# STLink_V3E_Module.net
KiCad netlist of a schematic drawn in Altium Designer
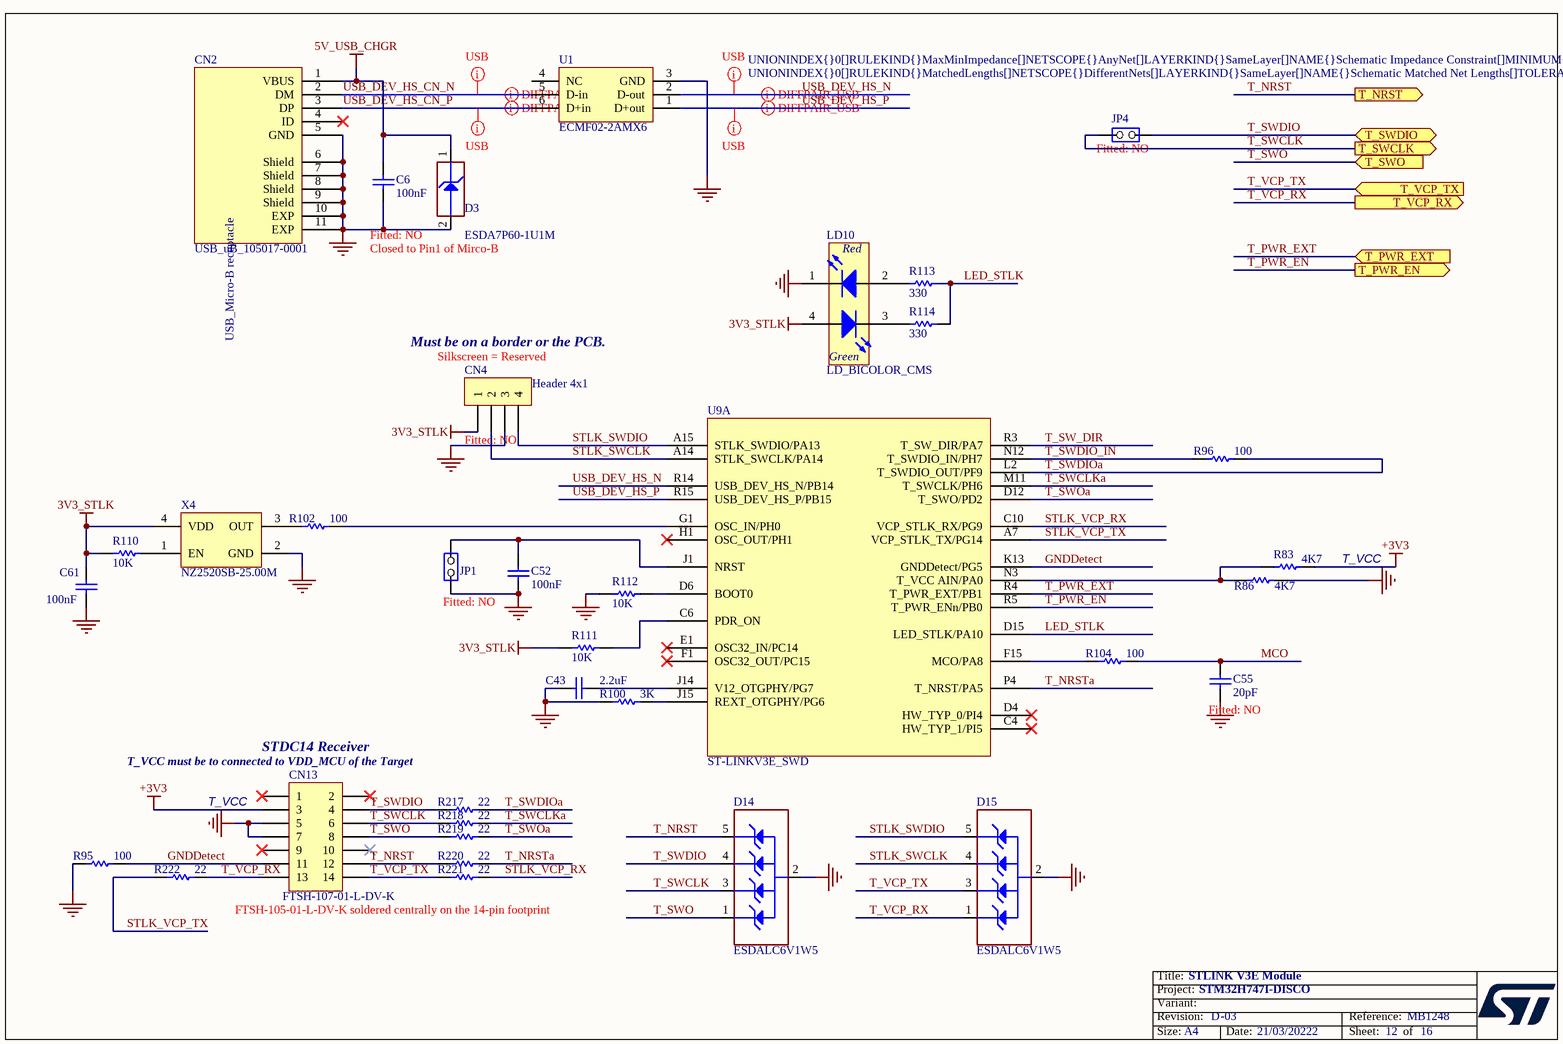
[diagram p0: STLink_V3E_Module.SchDoc]

(export (version "E")
  (design (tool "Eeschema 10.0.6"))
  (components
    (comp (ref "C6")
      (value "100nF")
      (footprint "0402C")
      (description "Capacitor,20pF,50V,NPO,5%,0402")
      (fields
        (field (name "INTERNAL_PART_NUMBER") "MCD-00016")
        (field (name "MANUFACTURER_PART_NUMBER") "CC0402JRNPO9BN200")
        (field (name "FITTED") "NO")
        (field (name "PROVIDED_BY") "Subcon")
      )
      (libsource (lib "MCD_PARTS_database") (part "Capacitor"))
    )
    (comp (ref "C43")
      (value "2.2uF")
      (footprint "0603C")
      (description "Capacitor,2.2uF,10V, X5R,10%,0603")
      (fields
        (field (name "INTERNAL_PART_NUMBER") "MCD-00012")
        (field (name "MANUFACTURER_PART_NUMBER") "CC0603KRX5R6BB225")
        (field (name "PROVIDED_BY") "Subcon")
      )
      (libsource (lib "MCD_PARTS_database") (part "Capacitor"))
    )
    (comp (ref "C52")
      (value "100nF")
      (footprint "0402C")
      (description "Capacitor,100nF,16V,X7R,10%,0402")
      (fields
        (field (name "INTERNAL_PART_NUMBER") "MCD-00102")
        (field (name "MANUFACTURER_PART_NUMBER") "CC0402KRX7R7BB104")
        (field (name "PROVIDED_BY") "Subcon")
      )
      (libsource (lib "MCD_PARTS_database") (part "Capacitor"))
    )
    (comp (ref "C55")
      (value "20pF")
      (footprint "0402C")
      (description "Capacitor,20pF,50V,NPO,5%,0402")
      (fields
        (field (name "INTERNAL_PART_NUMBER") "MCD-00016")
        (field (name "MANUFACTURER_PART_NUMBER") "CC0402JRNPO9BN200")
        (field (name "FITTED") "NO")
        (field (name "PROVIDED_BY") "Subcon")
      )
      (libsource (lib "MCD_PARTS_database") (part "Capacitor"))
    )
    (comp (ref "C61")
      (value "100nF")
      (footprint "0402C")
      (description "Capacitor,100nF,16V,X7R,10%,0402")
      (fields
        (field (name "INTERNAL_PART_NUMBER") "MCD-00102")
        (field (name "MANUFACTURER_PART_NUMBER") "CC0402KRX7R7BB104")
        (field (name "PROVIDED_BY") "Subcon")
      )
      (libsource (lib "MCD_PARTS_database") (part "Capacitor"))
    )
    (comp (ref "CN2")
      (value "USB_uB_105017-0001")
      (footprint "MICRO_USB_B_105017")
      (description "USB-MICRO-B, 0.65mm, RA, SMT, Bottom Mount,")
      (fields
        (field (name "INTERNAL_PART_NUMBER") "MCD-00028")
        (field (name "MANUFACTURER_PART_NUMBER") "1050170001")
        (field (name "PROVIDED_BY") "Subcon")
      )
      (libsource (lib "MCD_PARTS_database") (part "USB_uB_105017.0001"))
    )
    (comp (ref "CN4")
      (value "Header 4x1")
      (footprint "HDR_1X4_2R54")
      (description "Header, 4x1, 2,54mm, VR, TH, Height 5.84mm/2.54mm")
      (fields
        (field (name "INTERNAL_PART_NUMBER") "MCD-00029")
        (field (name "MANUFACTURER_PART_NUMBER") "TSW-104-07-x-S")
        (field (name "FITTED") "NO")
        (field (name "PROVIDED_BY") "Subcon")
      )
      (libsource (lib "MCD_PARTS_database") (part "Header 4x1"))
    )
    (comp (ref "CN13")
      (value "FTSH-107-01-L-DV-K")
      (footprint "FTSH-107-01-L-DV_B")
      (description "Header 7x2, 1.27mm, Dual row, Straight")
      (fields
        (field (name "INTERNAL_PART_NUMBER") "MCD-00592")
        (field (name "MANUFACTURER_PART_NUMBER") "FTSH-107-01-L-DV-009-ES-A")
        (field (name "PROVIDED_BY") "Subcon")
      )
      (libsource (lib "MCD_PARTS_database") (part "Header 7x2"))
    )
    (comp (ref "D3")
      (value "ESDA7P60-1U1M")
      (footprint "DO_2SM_1R6X1_21")
      (description "Dual Transil array for ESD protection")
      (libsource (lib "MCD_TEMP_PCH") (part "ESDALC6V1-1U2"))
    )
    (comp (ref "D14")
      (value "ESDALC6V1W5")
      (footprint "SC70-5")
      (description "Dual Transil array for ESD protection")
      (libsource (lib "MB1167_1") (part "ESDALC6V1W5"))
    )
    (comp (ref "D15")
      (value "ESDALC6V1W5")
      (footprint "SC70-5")
      (description "Dual Transil array for ESD protection")
      (libsource (lib "MB1167_1") (part "ESDALC6V1W5"))
    )
    (comp (ref "JP1")
      (value "Jumper Header 2x1")
      (footprint "SIP2")
      (description "Header, 2x1, 2,54mm, VR, TH, Height 5.84mm/2.54mm")
      (fields
        (field (name "INTERNAL_PART_NUMBER") "MCD-00045")
        (field (name "MANUFACTURER_PART_NUMBER") "TSW-102-07-x-S")
        (field (name "FITTED") "NO")
        (field (name "PROVIDED_BY") "Subcon")
      )
      (libsource (lib "MCD_PARTS_database") (part "Jumper Header 2x1"))
    )
    (comp (ref "JP4")
      (value "Jumper Header 2x1")
      (footprint "SIP2")
      (description "Header, 2x1, 2,54mm, VR, TH, Height 5.84mm/2.54mm")
      (fields
        (field (name "INTERNAL_PART_NUMBER") "MCD-00045")
        (field (name "MANUFACTURER_PART_NUMBER") "TSW-102-07-x-S")
        (field (name "FITTED") "NO")
        (field (name "PROVIDED_BY") "Subcon")
      )
      (libsource (lib "MCD_PARTS_database") (part "Jumper Header 2x1"))
    )
    (comp (ref "LD10")
      (value "LD_BICOLOR_CMS")
      (footprint "LED2_3528")
      (description "LED Bicolor")
      (fields
        (field (name "INTERNAL_PART_NUMBER") "MCD-00051")
        (field (name "MANUFACTURER_PART_NUMBER") "HSMF-A201-A00J1")
        (field (name "PROVIDED_BY") "Subcon")
      )
      (libsource (lib "MCD_PARTS_database") (part "LD_BICOLOR_CMS"))
    )
    (comp (ref "R83")
      (value "4K7")
      (footprint "0402R")
      (description "Resistor,4K7,0402,1%,1/16W")
      (fields
        (field (name "INTERNAL_PART_NUMBER") "MCD-00065")
        (field (name "MANUFACTURER_PART_NUMBER") "RC0402FR-074K7L")
        (field (name "PROVIDED_BY") "Subcon")
      )
      (libsource (lib "MCD_PARTS_database") (part "Resistor"))
    )
    (comp (ref "R86")
      (value "4K7")
      (footprint "0402R")
      (description "Resistor,4K7,0402,1%,1/16W")
      (fields
        (field (name "INTERNAL_PART_NUMBER") "MCD-00065")
        (field (name "MANUFACTURER_PART_NUMBER") "RC0402FR-074K7L")
        (field (name "PROVIDED_BY") "Subcon")
      )
      (libsource (lib "MCD_PARTS_database") (part "Resistor"))
    )
    (comp (ref "R95")
      (value "100")
      (footprint "0402R")
      (description "Resistor,100R,0402,1%,1/16W")
      (fields
        (field (name "INTERNAL_PART_NUMBER") "MCD-00119")
        (field (name "MANUFACTURER_PART_NUMBER") "RC0402FR-07100RL")
        (field (name "PROVIDED_BY") "Subcon")
      )
      (libsource (lib "MCD_PARTS_database") (part "Resistor"))
    )
    (comp (ref "R96")
      (value "100")
      (footprint "0402R")
      (description "Resistor,100R,0402,1%,1/16W")
      (fields
        (field (name "INTERNAL_PART_NUMBER") "MCD-00119")
        (field (name "MANUFACTURER_PART_NUMBER") "RC0402FR-07100RL")
        (field (name "PROVIDED_BY") "Subcon")
      )
      (libsource (lib "MCD_PARTS_database") (part "Resistor"))
    )
    (comp (ref "R100")
      (value "3K")
      (footprint "0402R")
      (description "Resistor,3K,0402,1%,1/16W")
      (fields
        (field (name "INTERNAL_PART_NUMBER") "MCD-00185")
        (field (name "MANUFACTURER_PART_NUMBER") "RC0402FR-073KL")
        (field (name "PROVIDED_BY") "Subcon")
      )
      (libsource (lib "MCD_PARTS_database") (part "Resistor"))
    )
    (comp (ref "R102")
      (value "100")
      (footprint "0402R")
      (description "Resistor,100R,0402,1%,1/16W")
      (fields
        (field (name "INTERNAL_PART_NUMBER") "MCD-00119")
        (field (name "MANUFACTURER_PART_NUMBER") "RC0402FR-07100RL")
        (field (name "PROVIDED_BY") "Subcon")
      )
      (libsource (lib "MCD_PARTS_database") (part "Resistor"))
    )
    (comp (ref "R104")
      (value "100")
      (footprint "0402R")
      (description "Resistor,100R,0402,1%,1/16W")
      (fields
        (field (name "INTERNAL_PART_NUMBER") "MCD-00119")
        (field (name "MANUFACTURER_PART_NUMBER") "RC0402FR-07100RL")
        (field (name "PROVIDED_BY") "Subcon")
      )
      (libsource (lib "MCD_PARTS_database") (part "Resistor"))
    )
    (comp (ref "R110")
      (value "10K")
      (footprint "0402R")
      (description "Resistor,10K,0402,1%,1/16W")
      (fields
        (field (name "INTERNAL_PART_NUMBER") "MCD-00053")
        (field (name "MANUFACTURER_PART_NUMBER") "RC0402FR-0710KL")
        (field (name "PROVIDED_BY") "subcon")
      )
      (libsource (lib "MCD_PARTS_database") (part "Resistor"))
    )
    (comp (ref "R111")
      (value "10K")
      (footprint "0402R")
      (description "Resistor,10K,0402,1%,1/16W")
      (fields
        (field (name "INTERNAL_PART_NUMBER") "MCD-00053")
        (field (name "MANUFACTURER_PART_NUMBER") "RC0402FR-0710KL")
        (field (name "PROVIDED_BY") "subcon")
      )
      (libsource (lib "MCD_PARTS_database") (part "Resistor"))
    )
    (comp (ref "R112")
      (value "10K")
      (footprint "0402R")
      (description "Resistor,10K,0402,1%,1/16W")
      (fields
        (field (name "INTERNAL_PART_NUMBER") "MCD-00053")
        (field (name "MANUFACTURER_PART_NUMBER") "RC0402FR-0710KL")
        (field (name "PROVIDED_BY") "subcon")
      )
      (libsource (lib "MCD_PARTS_database") (part "Resistor"))
    )
    (comp (ref "R113")
      (value "330")
      (footprint "0603R")
      (description "Resistor,330R,0603,1%,1/10W")
      (fields
        (field (name "INTERNAL_PART_NUMBER") "MCD-00197")
        (field (name "MANUFACTURER_PART_NUMBER") "RC0603FR-07330RL")
        (field (name "PROVIDED_BY") "Subcon")
      )
      (libsource (lib "MCD_PARTS_database") (part "Resistor"))
    )
    (comp (ref "R114")
      (value "330")
      (footprint "0603R")
      (description "Resistor,330R,0603,1%,1/10W")
      (fields
        (field (name "INTERNAL_PART_NUMBER") "MCD-00197")
        (field (name "MANUFACTURER_PART_NUMBER") "RC0603FR-07330RL")
        (field (name "PROVIDED_BY") "Subcon")
      )
      (libsource (lib "MCD_PARTS_database") (part "Resistor"))
    )
    (comp (ref "R217")
      (value "22")
      (footprint "0603R")
      (description "Resistor")
      (fields (field (name "PUBLISHER") "Altium Limited"))
      (libsource (lib "Miscellaneous Devices") (part "Res1"))
    )
    (comp (ref "R218")
      (value "22")
      (footprint "0603R")
      (description "Resistor")
      (fields (field (name "PUBLISHER") "Altium Limited"))
      (libsource (lib "Miscellaneous Devices") (part "Res1"))
    )
    (comp (ref "R219")
      (value "22")
      (footprint "0603R")
      (description "Resistor")
      (fields (field (name "PUBLISHER") "Altium Limited"))
      (libsource (lib "Miscellaneous Devices") (part "Res1"))
    )
    (comp (ref "R220")
      (value "22")
      (footprint "0603R")
      (description "Resistor")
      (fields (field (name "PUBLISHER") "Altium Limited"))
      (libsource (lib "Miscellaneous Devices") (part "Res1"))
    )
    (comp (ref "R221")
      (value "22")
      (footprint "0603R")
      (description "Resistor")
      (fields (field (name "PUBLISHER") "Altium Limited"))
      (libsource (lib "Miscellaneous Devices") (part "Res1"))
    )
    (comp (ref "R222")
      (value "22")
      (footprint "0603R")
      (description "Resistor")
      (fields (field (name "PUBLISHER") "Altium Limited"))
      (libsource (lib "Miscellaneous Devices") (part "Res1"))
    )
    (comp (ref "U1")
      (value "ECMF02-2AMX6")
      (footprint "DFN6_0R5_1R7X1R5")
      (description "Common mode filter with ESD protection for USB 2.0 interface")
      (libsource (lib "MB1248_1") (part "ECMF02-2AMX6"))
    )
    (comp (ref "U9")
      (value "ST-LINKV3E_SWD")
      (footprint "BGA176_0R65_10x10")
      (description "STM32F723IEK  (STM32F7 LittleBirdie) BGA176")
      (fields (field (name "INTERNAL_PART_NUMBER") "MCD-00596"))
      (libsource (lib "MB1248_1") (part "ST-LINKV3E_SWD"))
    )
    (comp (ref "X4")
      (value "NZ2520SB-25.00M")
      (footprint "OSC_4SM_2R5X2")
      (description "Oscillator 25.00Mhz, -+50PPM, 3.3V, Temp -55 to +125癈")
      (libsource (lib "MCD_TOOLS") (part "OSC_25M_NZ2520SB"))
    )
  )
  (nets
    (net (code "1") (name "+3V3") (class "Default")
      (node (ref "CN13") (pin "3") (pinfunction "3_3") (pintype "passive"))
      (node (ref "R83") (pin "2") (pinfunction "2_2") (pintype "passive"))
    )
    (net (code "2") (name "/GNDDetect") (class "Default")
      (node (ref "CN13") (pin "11") (pinfunction "11_11") (pintype "passive"))
      (node (ref "R95") (pin "2") (pinfunction "2_2") (pintype "passive"))
      (node (ref "U9") (pin "K13") (pinfunction "GNDDetect/PG5_K13") (pintype "passive"))
    )
    (net (code "3") (name "/LED_STLK") (class "Default")
      (node (ref "R113") (pin "2") (pinfunction "2_2") (pintype "passive"))
      (node (ref "R114") (pin "2") (pinfunction "2_2") (pintype "passive"))
      (node (ref "U9") (pin "D15") (pinfunction "LED_STLK/PA10_D15") (pintype "passive"))
    )
    (net (code "4") (name "/MCO") (class "Default")
      (node (ref "C55") (pin "2") (pinfunction "2_2") (pintype "passive"))
      (node (ref "R104") (pin "2") (pinfunction "2_2") (pintype "passive"))
    )
    (net (code "5") (name "/STLK_SWCLK") (class "Default")
      (node (ref "CN4") (pin "2") (pinfunction "2_2") (pintype "passive"))
      (node (ref "D15") (pin "4") (pinfunction "IO3_4") (pintype "passive"))
      (node (ref "U9") (pin "A14") (pinfunction "STLK_SWCLK/PA14_A14") (pintype "passive"))
    )
    (net (code "6") (name "/STLK_SWDIO") (class "Default")
      (node (ref "CN4") (pin "4") (pinfunction "4_4") (pintype "passive"))
      (node (ref "D15") (pin "5") (pinfunction "IO4_5") (pintype "passive"))
      (node (ref "U9") (pin "A15") (pinfunction "STLK_SWDIO/PA13_A15") (pintype "passive"))
    )
    (net (code "7") (name "/STLK_VCP_RX") (class "Default")
      (node (ref "R221") (pin "1") (pinfunction "1_1") (pintype "passive"))
      (node (ref "U9") (pin "C10") (pinfunction "VCP_STLK_RX/PG9_C10") (pintype "passive"))
    )
    (net (code "8") (name "/STLK_VCP_TX") (class "Default")
      (node (ref "R222") (pin "2") (pinfunction "2_2") (pintype "passive"))
      (node (ref "U9") (pin "A7") (pinfunction "VCP_STLK_TX/PG14_A7") (pintype "passive"))
    )
    (net (code "9") (name "/T_NRST") (class "Default")
      (node (ref "CN13") (pin "12") (pinfunction "12_12") (pintype "passive"))
      (node (ref "D14") (pin "5") (pinfunction "IO4_5") (pintype "passive"))
      (node (ref "R220") (pin "2") (pinfunction "2_2") (pintype "passive"))
    )
    (net (code "10") (name "/T_NRSTa") (class "Default")
      (node (ref "R220") (pin "1") (pinfunction "1_1") (pintype "passive"))
      (node (ref "U9") (pin "P4") (pinfunction "T_NRST/PA5_P4") (pintype "passive"))
    )
    (net (code "11") (name "/T_PWR_EN") (class "Default")
      (node (ref "U9") (pin "R5") (pinfunction "T_PWR_ENn/PB0_R5") (pintype "passive"))
    )
    (net (code "12") (name "/T_PWR_EXT") (class "Default")
      (node (ref "U9") (pin "R4") (pinfunction "T_PWR_EXT/PB1_R4") (pintype "passive"))
    )
    (net (code "13") (name "/T_SWCLK") (class "Default")
      (node (ref "CN13") (pin "6") (pinfunction "6_6") (pintype "passive"))
      (node (ref "D14") (pin "3") (pinfunction "IO2_3") (pintype "passive"))
      (node (ref "JP4") (pin "1") (pinfunction "COMMON_1") (pintype "passive"))
      (node (ref "R218") (pin "2") (pinfunction "2_2") (pintype "passive"))
    )
    (net (code "14") (name "/T_SWCLKa") (class "Default")
      (node (ref "R218") (pin "1") (pinfunction "1_1") (pintype "passive"))
      (node (ref "U9") (pin "M11") (pinfunction "T_SWCLK/PH6_M11") (pintype "passive"))
    )
    (net (code "15") (name "/T_SWDIO") (class "Default")
      (node (ref "CN13") (pin "4") (pinfunction "4_4") (pintype "passive"))
      (node (ref "D14") (pin "4") (pinfunction "IO3_4") (pintype "passive"))
      (node (ref "JP4") (pin "2") (pinfunction "NO_2") (pintype "passive"))
      (node (ref "R217") (pin "2") (pinfunction "2_2") (pintype "passive"))
    )
    (net (code "16") (name "/T_SWDIO_IN") (class "Default")
      (node (ref "R96") (pin "1") (pinfunction "1_1") (pintype "passive"))
      (node (ref "U9") (pin "N12") (pinfunction "T_SWDIO_IN/PH7_N12") (pintype "passive"))
    )
    (net (code "17") (name "/T_SWDIOa") (class "Default")
      (node (ref "R217") (pin "1") (pinfunction "1_1") (pintype "passive"))
      (node (ref "R96") (pin "2") (pinfunction "2_2") (pintype "passive"))
      (node (ref "U9") (pin "L2") (pinfunction "T_SWDIO_OUT/PF9_L2") (pintype "passive"))
    )
    (net (code "18") (name "/T_SWO") (class "Default")
      (node (ref "CN13") (pin "8") (pinfunction "8_8") (pintype "passive"))
      (node (ref "D14") (pin "1") (pinfunction "IO1_1") (pintype "passive"))
      (node (ref "R219") (pin "2") (pinfunction "2_2") (pintype "passive"))
    )
    (net (code "19") (name "/T_SWOa") (class "Default")
      (node (ref "R219") (pin "1") (pinfunction "1_1") (pintype "passive"))
      (node (ref "U9") (pin "D12") (pinfunction "T_SWO/PD2_D12") (pintype "passive"))
    )
    (net (code "20") (name "/T_SW_DIR") (class "Default")
      (node (ref "U9") (pin "R3") (pinfunction "T_SW_DIR/PA7_R3") (pintype "passive"))
    )
    (net (code "21") (name "/T_VCP_RX") (class "Default")
      (node (ref "CN13") (pin "13") (pinfunction "13_13") (pintype "passive"))
      (node (ref "D15") (pin "1") (pinfunction "IO1_1") (pintype "passive"))
      (node (ref "R222") (pin "1") (pinfunction "1_1") (pintype "passive"))
    )
    (net (code "22") (name "/T_VCP_TX") (class "Default")
      (node (ref "CN13") (pin "14") (pinfunction "14_14") (pintype "passive"))
      (node (ref "D15") (pin "3") (pinfunction "IO2_3") (pintype "passive"))
      (node (ref "R221") (pin "2") (pinfunction "2_2") (pintype "passive"))
    )
    (net (code "23") (name "/USB_DEV_HS_CN_N") (class "Default")
      (node (ref "CN2") (pin "2") (pinfunction "DM_2") (pintype "passive"))
      (node (ref "U1") (pin "5") (pinfunction "D-in_5") (pintype "passive"))
    )
    (net (code "24") (name "/USB_DEV_HS_CN_P") (class "Default")
      (node (ref "CN2") (pin "3") (pinfunction "DP_3") (pintype "passive"))
      (node (ref "U1") (pin "6") (pinfunction "D+in_6") (pintype "passive"))
    )
    (net (code "25") (name "/USB_DEV_HS_N") (class "Default")
      (node (ref "U1") (pin "2") (pinfunction "D-out_2") (pintype "passive"))
      (node (ref "U9") (pin "R14") (pinfunction "USB_DEV_HS_N/PB14_R14") (pintype "passive"))
    )
    (net (code "26") (name "/USB_DEV_HS_P") (class "Default")
      (node (ref "U1") (pin "1") (pinfunction "D+out_1") (pintype "passive"))
      (node (ref "U9") (pin "R15") (pinfunction "USB_DEV_HS_P/PB15_R15") (pintype "passive"))
    )
    (net (code "27") (name "3V3_STLK") (class "Default")
      (node (ref "C61") (pin "2") (pinfunction "2_2") (pintype "passive"))
      (node (ref "CN4") (pin "1") (pinfunction "1_1") (pintype "passive"))
      (node (ref "LD10") (pin "4") (pinfunction "YellowGreen_anode_4") (pintype "passive"))
      (node (ref "R110") (pin "1") (pinfunction "1_1") (pintype "passive"))
      (node (ref "R111") (pin "1") (pinfunction "1_1") (pintype "passive"))
      (node (ref "X4") (pin "4") (pinfunction "VDD_4") (pintype "passive"))
    )
    (net (code "28") (name "5V_USB_CHGR") (class "Default")
      (node (ref "C6") (pin "2") (pinfunction "2_2") (pintype "passive"))
      (node (ref "CN2") (pin "1") (pinfunction "VBUS_1") (pintype "passive"))
      (node (ref "D3") (pin "1") (pinfunction "IO1_1") (pintype "passive"))
    )
    (net (code "29") (name "GND") (class "Default")
      (node (ref "C43") (pin "1") (pinfunction "1_1") (pintype "passive"))
      (node (ref "C52") (pin "1") (pinfunction "1_1") (pintype "passive"))
      (node (ref "C55") (pin "1") (pinfunction "1_1") (pintype "passive"))
      (node (ref "C6") (pin "1") (pinfunction "1_1") (pintype "passive"))
      (node (ref "C61") (pin "1") (pinfunction "1_1") (pintype "passive"))
      (node (ref "CN13") (pin "5") (pinfunction "5_5") (pintype "passive"))
      (node (ref "CN13") (pin "7") (pinfunction "7_7") (pintype "passive"))
      (node (ref "CN2") (pin "10") (pinfunction "EXP_10") (pintype "passive"))
      (node (ref "CN2") (pin "11") (pinfunction "EXP_11") (pintype "passive"))
      (node (ref "CN2") (pin "5") (pinfunction "GND_5") (pintype "passive"))
      (node (ref "CN2") (pin "6") (pinfunction "Shield_6") (pintype "passive"))
      (node (ref "CN2") (pin "7") (pinfunction "Shield_7") (pintype "passive"))
      (node (ref "CN2") (pin "8") (pinfunction "Shield_8") (pintype "passive"))
      (node (ref "CN2") (pin "9") (pinfunction "Shield_9") (pintype "passive"))
      (node (ref "CN4") (pin "3") (pinfunction "3_3") (pintype "passive"))
      (node (ref "D14") (pin "2") (pinfunction "GND_2") (pintype "passive"))
      (node (ref "D15") (pin "2") (pinfunction "GND_2") (pintype "passive"))
      (node (ref "D3") (pin "2") (pinfunction "GND_2") (pintype "passive"))
      (node (ref "JP1") (pin "1") (pinfunction "COMMON_1") (pintype "passive"))
      (node (ref "LD10") (pin "1") (pinfunction "RED_cathode_1") (pintype "passive"))
      (node (ref "R100") (pin "1") (pinfunction "1_1") (pintype "passive"))
      (node (ref "R112") (pin "1") (pinfunction "1_1") (pintype "passive"))
      (node (ref "R86") (pin "2") (pinfunction "2_2") (pintype "passive"))
      (node (ref "R95") (pin "1") (pinfunction "1_1") (pintype "passive"))
      (node (ref "U1") (pin "3") (pinfunction "GND_3") (pintype "passive"))
      (node (ref "X4") (pin "2") (pinfunction "GND_2") (pintype "passive"))
    )
    (net (code "30") (name "Net-(JP1-NO)") (class "Default")
      (node (ref "C52") (pin "2") (pinfunction "2_2") (pintype "passive"))
      (node (ref "JP1") (pin "2") (pinfunction "NO_2") (pintype "passive"))
      (node (ref "U9") (pin "J1") (pinfunction "NRST_J1") (pintype "passive"))
    )
    (net (code "31") (name "Net-(LD10-Red_anode)") (class "Default")
      (node (ref "LD10") (pin "2") (pinfunction "Red_anode_2") (pintype "passive"))
      (node (ref "R113") (pin "1") (pinfunction "1_1") (pintype "passive"))
    )
    (net (code "32") (name "Net-(LD10-YellowGreen_cathode)") (class "Default")
      (node (ref "LD10") (pin "3") (pinfunction "YellowGreen_cathode_3") (pintype "passive"))
      (node (ref "R114") (pin "1") (pinfunction "1_1") (pintype "passive"))
    )
    (net (code "33") (name "Net-(U9A-BOOT0)") (class "Default")
      (node (ref "R112") (pin "2") (pinfunction "2_2") (pintype "passive"))
      (node (ref "U9") (pin "D6") (pinfunction "BOOT0_D6") (pintype "passive"))
    )
    (net (code "34") (name "Net-(U9A-MCO{slash}PA8)") (class "Default")
      (node (ref "R104") (pin "1") (pinfunction "1_1") (pintype "passive"))
      (node (ref "U9") (pin "F15") (pinfunction "MCO/PA8_F15") (pintype "passive"))
    )
    (net (code "35") (name "Net-(U9A-OSC_IN{slash}PH0)") (class "Default")
      (node (ref "R102") (pin "2") (pinfunction "2_2") (pintype "passive"))
      (node (ref "U9") (pin "G1") (pinfunction "OSC_IN/PH0_G1") (pintype "passive"))
    )
    (net (code "36") (name "Net-(U9A-PDR_ON)") (class "Default")
      (node (ref "R111") (pin "2") (pinfunction "2_2") (pintype "passive"))
      (node (ref "U9") (pin "C6") (pinfunction "PDR_ON_C6") (pintype "passive"))
    )
    (net (code "37") (name "Net-(U9A-REXT_OTGPHY{slash}PG6)") (class "Default")
      (node (ref "R100") (pin "2") (pinfunction "2_2") (pintype "passive"))
      (node (ref "U9") (pin "J15") (pinfunction "REXT_OTGPHY/PG6_J15") (pintype "passive"))
    )
    (net (code "38") (name "Net-(U9A-T_VCC_AIN{slash}PA0)") (class "Default")
      (node (ref "R83") (pin "1") (pinfunction "1_1") (pintype "passive"))
      (node (ref "R86") (pin "1") (pinfunction "1_1") (pintype "passive"))
      (node (ref "U9") (pin "N3") (pinfunction "T_VCC_AIN/PA0_N3") (pintype "passive"))
    )
    (net (code "39") (name "Net-(U9A-V12_OTGPHY{slash}PG7)") (class "Default")
      (node (ref "C43") (pin "2") (pinfunction "2_2") (pintype "passive"))
      (node (ref "U9") (pin "J14") (pinfunction "V12_OTGPHY/PG7_J14") (pintype "passive"))
    )
    (net (code "40") (name "Net-(X4-EN)") (class "Default")
      (node (ref "R110") (pin "2") (pinfunction "2_2") (pintype "passive"))
      (node (ref "X4") (pin "1") (pinfunction "EN_1") (pintype "passive"))
    )
    (net (code "41") (name "Net-(X4-OUT)") (class "Default")
      (node (ref "R102") (pin "1") (pinfunction "1_1") (pintype "passive"))
      (node (ref "X4") (pin "3") (pinfunction "OUT_3") (pintype "passive"))
    )
    (net (code "42") (name "unconnected-(CN2-ID-Pad4)") (class "Default")
      (node (ref "CN2") (pin "4") (pinfunction "ID_4") (pintype "passive+no_connect"))
    )
    (net (code "43") (name "unconnected-(CN13-Pad1)") (class "Default")
      (node (ref "CN13") (pin "1") (pinfunction "1_1") (pintype "passive+no_connect"))
    )
    (net (code "44") (name "unconnected-(CN13-Pad2)") (class "Default")
      (node (ref "CN13") (pin "2") (pinfunction "2_2") (pintype "passive+no_connect"))
    )
    (net (code "45") (name "unconnected-(CN13-Pad9)") (class "Default")
      (node (ref "CN13") (pin "9") (pinfunction "9_9") (pintype "passive+no_connect"))
    )
    (net (code "46") (name "unconnected-(CN13-Pad10)") (class "Default")
      (node (ref "CN13") (pin "10") (pinfunction "10_10") (pintype "passive+no_connect"))
    )
    (net (code "47") (name "unconnected-(U1-NC-Pad4)") (class "Default")
      (node (ref "U1") (pin "4") (pinfunction "NC_4") (pintype "passive"))
    )
    (net (code "48") (name "unconnected-(U9A-HW_TYP_0{slash}PI4-PadD4)") (class "Default")
      (node (ref "U9") (pin "D4") (pinfunction "HW_TYP_0/PI4_D4") (pintype "passive+no_connect"))
    )
    (net (code "49") (name "unconnected-(U9A-HW_TYP_1{slash}PI5-PadC4)") (class "Default")
      (node (ref "U9") (pin "C4") (pinfunction "HW_TYP_1/PI5_C4") (pintype "passive+no_connect"))
    )
    (net (code "50") (name "unconnected-(U9A-OSC32_IN{slash}PC14-PadE1)") (class "Default")
      (node (ref "U9") (pin "E1") (pinfunction "OSC32_IN/PC14_E1") (pintype "passive+no_connect"))
    )
    (net (code "51") (name "unconnected-(U9A-OSC32_OUT{slash}PC15-PadF1)") (class "Default")
      (node (ref "U9") (pin "F1") (pinfunction "OSC32_OUT/PC15_F1") (pintype "passive+no_connect"))
    )
    (net (code "52") (name "unconnected-(U9A-OSC_OUT{slash}PH1-PadH1)") (class "Default")
      (node (ref "U9") (pin "H1") (pinfunction "OSC_OUT/PH1_H1") (pintype "passive+no_connect"))
    )
  )
)
